# Sheet1.net
KiCad netlist of a schematic drawn in Altium Designer
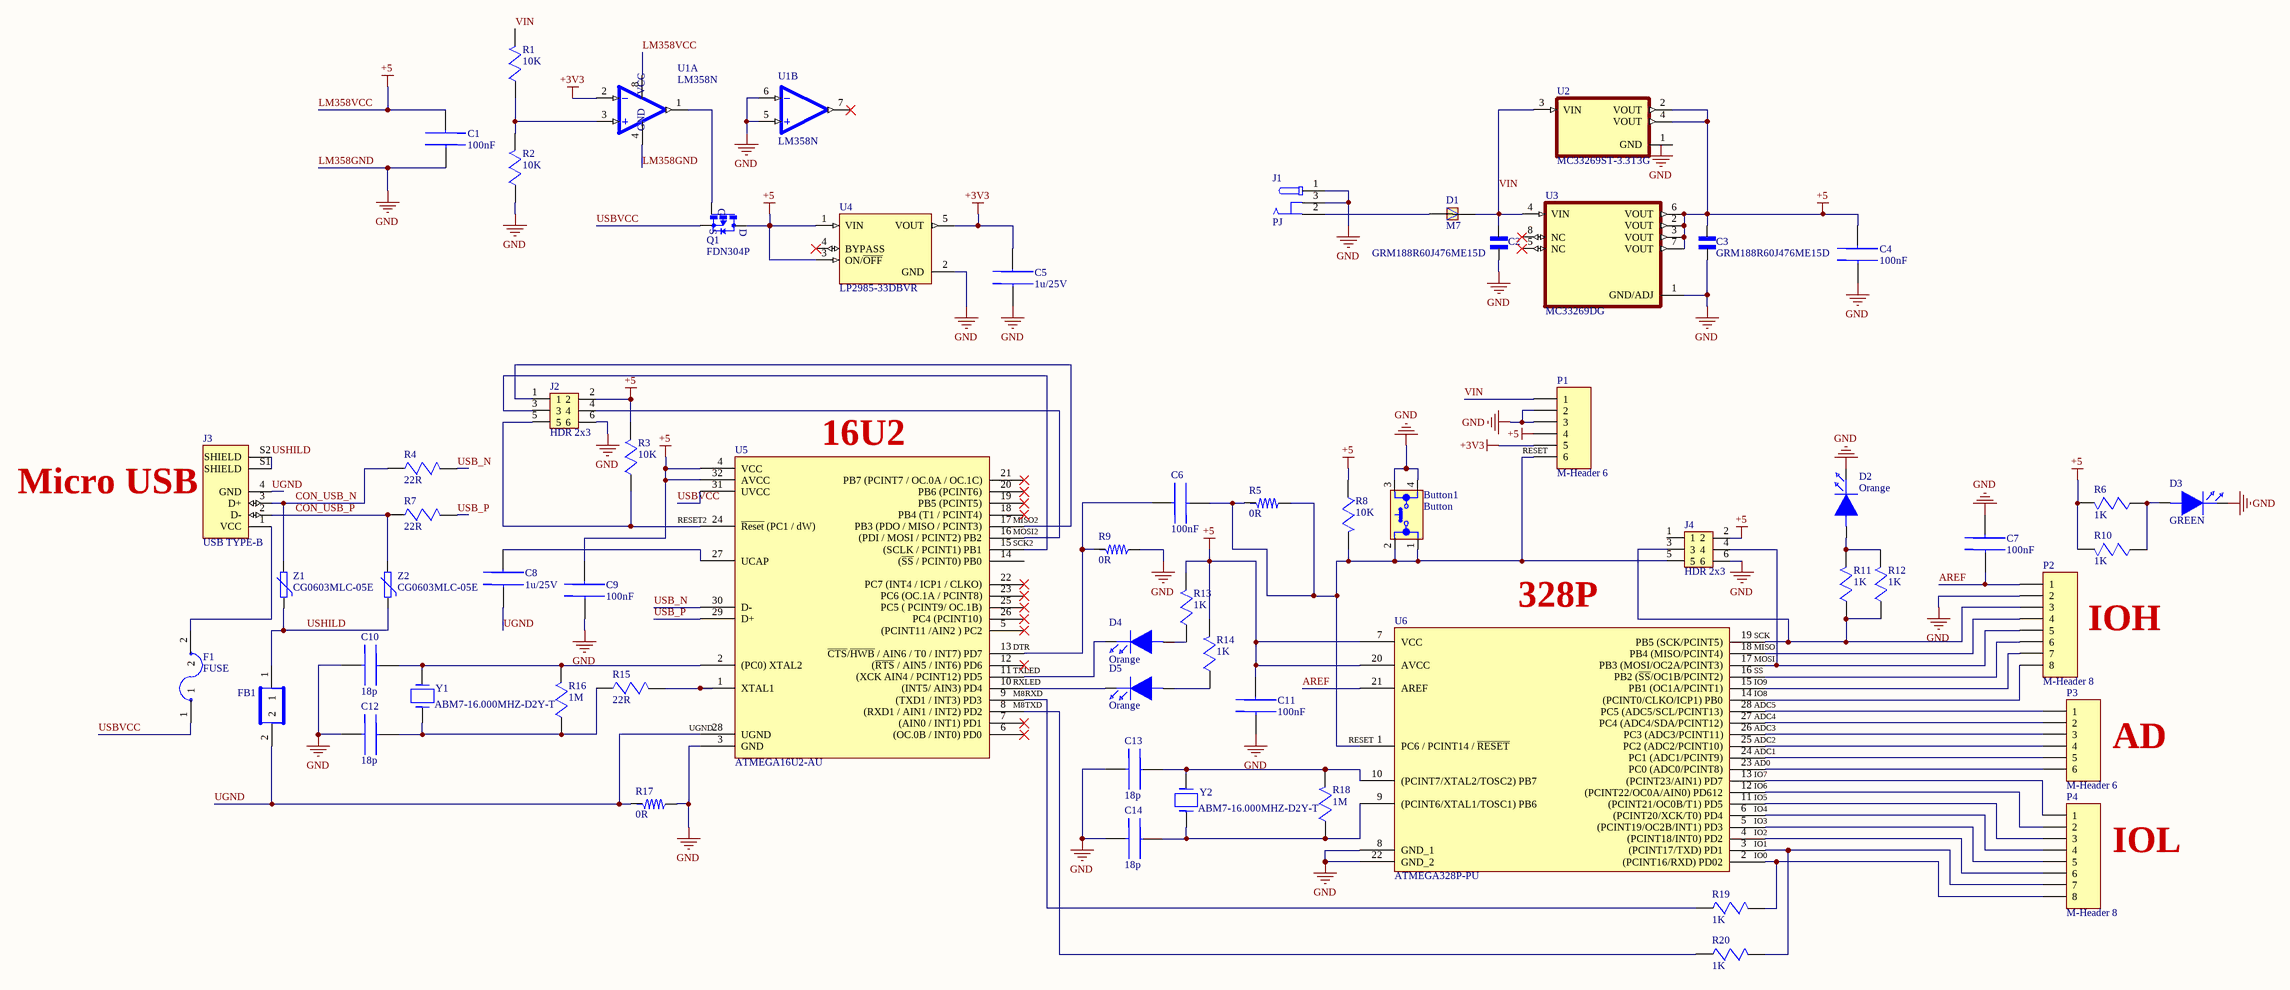
[diagram p0: Sheet1.SchDoc]

(export (version "E")
  (design (tool "Eeschema 10.0.6"))
  (components
    (comp (ref "Button1")
      (value "Button")
      (footprint "1825910-6_BUTTON")
      (description "SWITCH TACTILE SPST-NO 0.05A 24V")
      (fields
        (field (name "MANUFACTURER") "TE Connectivity Alcoswitch")
        (field (name "MANUFACTURER PART NUMBER") "1825910-6")
      )
      (libsource (lib "28_Pin Project V1.1_shematics_libraries") (part "1825910-6"))
    )
    (comp (ref "C1")
      (value "100nF")
      (footprint "C0805")
      (fields
        (field (name "MANUFACTURER") "TDK")
        (field (name "MANUFACTURER PART NUMBER") "C2012X7R1H104K085AA")
        (field (name "TOLERANCE") "10%")
      )
      (libsource (lib "28_Pin Project V1.1_shematics_libraries") (part "C2012X7R1H104K085AA"))
    )
    (comp (ref "C2")
      (value "GRM188R60J476ME15D")
      (footprint "CAPC1608X100N")
      (description "SMD capacitor X5R(EIA) with capacitance 47uF Tol.20%. Rated voltage 6.3Vdc 85C")
      (fields (field (name "MF") "Murata"))
      (libsource (lib "GRM188R60J476ME15D") (part "GRM188R60J476ME15D"))
    )
    (comp (ref "C3")
      (value "GRM188R60J476ME15D")
      (footprint "CAPC1608X100N")
      (description "SMD capacitor X5R(EIA) with capacitance 47uF Tol.20%. Rated voltage 6.3Vdc 85C")
      (fields (field (name "MF") "Murata"))
      (libsource (lib "GRM188R60J476ME15D") (part "GRM188R60J476ME15D"))
    )
    (comp (ref "C4")
      (value "100nF")
      (footprint "C0805")
      (fields
        (field (name "MANUFACTURER") "TDK")
        (field (name "MANUFACTURER PART NUMBER") "C2012X7R1H104K085AA")
        (field (name "TOLERANCE") "10%")
      )
      (libsource (lib "28_Pin Project V1.1_shematics_libraries") (part "C2012X7R1H104K085AA"))
    )
    (comp (ref "C5")
      (value "1u/25V")
      (footprint "C0805")
      (fields
        (field (name "MANUFACTURER") "TDK")
        (field (name "MANUFACTURER PART NUMBER") "C2012X5R1E105K125AA")
        (field (name "TOLERANCE") "10%")
      )
      (libsource (lib "28_Pin Project V1.1_shematics_libraries") (part "C2012X5R1E105K125AA"))
    )
    (comp (ref "C6")
      (value "100nF")
      (footprint "C0805")
      (fields
        (field (name "MANUFACTURER") "TDK")
        (field (name "MANUFACTURER PART NUMBER") "C2012X7R1H104K085AA")
        (field (name "TOLERANCE") "10%")
      )
      (libsource (lib "28_Pin Project V1.1_shematics_libraries") (part "C2012X7R1H104K085AA"))
    )
    (comp (ref "C7")
      (value "100nF")
      (footprint "C0805")
      (fields
        (field (name "MANUFACTURER") "TDK")
        (field (name "MANUFACTURER PART NUMBER") "C2012X7R1H104K085AA")
        (field (name "TOLERANCE") "10%")
      )
      (libsource (lib "28_Pin Project V1.1_shematics_libraries") (part "C2012X7R1H104K085AA"))
    )
    (comp (ref "C8")
      (value "1u/25V")
      (footprint "C0805")
      (fields
        (field (name "MANUFACTURER") "TDK")
        (field (name "MANUFACTURER PART NUMBER") "C2012X5R1E105K125AA")
        (field (name "TOLERANCE") "10%")
      )
      (libsource (lib "28_Pin Project V1.1_shematics_libraries") (part "C2012X5R1E105K125AA"))
    )
    (comp (ref "C9")
      (value "100nF")
      (footprint "C0805")
      (fields
        (field (name "MANUFACTURER") "TDK")
        (field (name "MANUFACTURER PART NUMBER") "C2012X7R1H104K085AA")
        (field (name "TOLERANCE") "10%")
      )
      (libsource (lib "28_Pin Project V1.1_shematics_libraries") (part "C2012X7R1H104K085AA"))
    )
    (comp (ref "C10")
      (value "18p")
      (footprint "C0805")
      (description "CAP CER 18PF 50V C0G/NP0 0805")
      (fields
        (field (name "MANUFACTURER") "KEMET")
        (field (name "MANUFACTURER PART NUMBER") "C0805C180J5GACTU")
      )
      (libsource (lib "28_Pin Project V1.1_shematics_libraries") (part "C0805C180J5GACTU"))
    )
    (comp (ref "C11")
      (value "100nF")
      (footprint "C0805")
      (fields
        (field (name "MANUFACTURER") "TDK")
        (field (name "MANUFACTURER PART NUMBER") "C2012X7R1H104K085AA")
        (field (name "TOLERANCE") "10%")
      )
      (libsource (lib "28_Pin Project V1.1_shematics_libraries") (part "C2012X7R1H104K085AA"))
    )
    (comp (ref "C12")
      (value "18p")
      (footprint "C0805")
      (description "CAP CER 18PF 50V C0G/NP0 0805")
      (fields
        (field (name "MANUFACTURER") "KEMET")
        (field (name "MANUFACTURER PART NUMBER") "C0805C180J5GACTU")
      )
      (libsource (lib "28_Pin Project V1.1_shematics_libraries") (part "C0805C180J5GACTU"))
    )
    (comp (ref "C13")
      (value "18p")
      (footprint "C0805")
      (description "CAP CER 18PF 50V C0G/NP0 0805")
      (fields
        (field (name "MANUFACTURER") "KEMET")
        (field (name "MANUFACTURER PART NUMBER") "C0805C180J5GACTU")
      )
      (libsource (lib "28_Pin Project V1.1_shematics_libraries") (part "C0805C180J5GACTU"))
    )
    (comp (ref "C14")
      (value "18p")
      (footprint "C0805")
      (description "CAP CER 18PF 50V C0G/NP0 0805")
      (fields
        (field (name "MANUFACTURER") "KEMET")
        (field (name "MANUFACTURER PART NUMBER") "C0805C180J5GACTU")
      )
      (libsource (lib "28_Pin Project V1.1_shematics_libraries") (part "C0805C180J5GACTU"))
    )
    (comp (ref "D1")
      (value "M7")
      (footprint "DIOM505270X240")
      (description "Diode, SMA, 1000V, 1A, 150Â°C")
      (fields (field (name "MF") "Diotec Semiconductor"))
      (libsource (lib "M7") (part "M7"))
    )
    (comp (ref "D2")
      (value "Orange")
      (footprint "Orange_LED")
      (description "OSRAM - LO L29K-H2K1-24-Z - SMARTLED 0603 ORANGE")
      (fields
        (field (name "MANUFACTURER") "Osram Opto")
        (field (name "MANUFACTURER PART NUMBER") "LOL29K-H2K1-24-Z")
      )
      (libsource (lib "28_Pin Project V1.1_shematics_libraries") (part "LOL29K-H2K1-24-Z"))
    )
    (comp (ref "D3")
      (value "GREEN")
      (footprint "Orange_LED")
      (description "LED Uni-Color Green 572nm 2-Pin Chip 0603(1608Metric) T/R")
      (fields
        (field (name "MANUFACTURER") "Osram Opto")
        (field (name "MANUFACTURER PART NUMBER") "LGL29K-G2J1-24-Z")
      )
      (libsource (lib "28_Pin Project V1.1_shematics_libraries") (part "LGL29K-G2J1-24-Z"))
    )
    (comp (ref "D4")
      (value "Orange")
      (footprint "Orange_LED")
      (description "OSRAM - LO L29K-H2K1-24-Z - SMARTLED 0603 ORANGE")
      (fields
        (field (name "MANUFACTURER") "Osram Opto")
        (field (name "MANUFACTURER PART NUMBER") "LOL29K-H2K1-24-Z")
      )
      (libsource (lib "28_Pin Project V1.1_shematics_libraries") (part "LOL29K-H2K1-24-Z"))
    )
    (comp (ref "D5")
      (value "Orange")
      (footprint "Orange_LED")
      (description "OSRAM - LO L29K-H2K1-24-Z - SMARTLED 0603 ORANGE")
      (fields
        (field (name "MANUFACTURER") "Osram Opto")
        (field (name "MANUFACTURER PART NUMBER") "LOL29K-H2K1-24-Z")
      )
      (libsource (lib "28_Pin Project V1.1_shematics_libraries") (part "LOL29K-H2K1-24-Z"))
    )
    (comp (ref "F1")
      (value "FUSE")
      (footprint "FUSM4632X85")
      (description "Polymeric PTC Resettable Fuse 15V 500 mA Ih Surface Mount 1812 (4532 Metric), Concave")
      (fields (field (name "MP") "MF-MSMF050-2") (field (name "MF") "Bourns"))
      (libsource (lib "ARDUINO-UNO") (part "FUSE"))
    )
    (comp (ref "FB1")
      (value "~")
      (footprint "C0805")
      (description "FERRITE BEAD 600 OHM 0805 1LN")
      (fields
        (field (name "MANUFACTURER") "TDK")
        (field (name "MANUFACTURER PART NUMBER") "MPZ2012S601AT000")
      )
      (libsource (lib "28_Pin Project V1.1_shematics_libraries") (part "MPZ2012S601AT000"))
    )
    (comp (ref "J1")
      (value "PJ")
      (footprint "MPD_EJ503A")
      (description "Power Barrel Connector Jack 2.10mm ID (0.083), 5.50mm OD (0.217) Through Hole, Right Angle")
      (fields (field (name "MF") "MPD") (field (name "MP") "EJ503A"))
      (libsource (lib "ARDUINO-UNO") (part "PJ"))
    )
    (comp (ref "J2")
      (value "HDR 2x3")
      (footprint "HDR_2x3_2.55mm")
      (description "CONN HEADER 6POS .100 STR 30AU")
      (fields
        (field (name "MANUFACTURER") "Amphenol FCI")
        (field (name "MANUFACTURER PART NUMBER") "67997-106HLF")
      )
      (libsource (lib "28_Pin Project V1.1_shematics_libraries") (part "67997-106HLF"))
    )
    (comp (ref "J3")
      (value "USB TYPE-B")
      (footprint "SAMTEC_USB-B-S-X-X-TH")
      (description "USB-B (USB TYPE-B) USB 2.0 Receptacle Connector 4 Position Through Hole, Right Angle")
      (fields (field (name "MF") "Samtec") (field (name "MP") "USB-B-S-F-W-TH-TR"))
      (libsource (lib "ARDUINO-UNO") (part "USB TYPE-B"))
    )
    (comp (ref "J4")
      (value "HDR 2x3")
      (footprint "HDR_2x3_2.55mm")
      (description "CONN HEADER 6POS .100 STR 30AU")
      (fields
        (field (name "MANUFACTURER") "Amphenol FCI")
        (field (name "MANUFACTURER PART NUMBER") "67997-106HLF")
      )
      (libsource (lib "28_Pin Project V1.1_shematics_libraries") (part "67997-106HLF"))
    )
    (comp (ref "P1")
      (value "M-Header 6")
      (footprint "M-Header 6")
      (libsource (lib "ARDUINO-UNO") (part "M-Header 6"))
    )
    (comp (ref "P2")
      (value "M-Header 8")
      (footprint "M-Header 8")
      (libsource (lib "ARDUINO-UNO") (part "M-Header 8"))
    )
    (comp (ref "P3")
      (value "M-Header 6")
      (footprint "M-Header 6")
      (libsource (lib "ARDUINO-UNO") (part "M-Header 6"))
    )
    (comp (ref "P4")
      (value "M-Header 8")
      (footprint "M-Header 8")
      (libsource (lib "ARDUINO-UNO") (part "M-Header 8"))
    )
    (comp (ref "Q1")
      (value "FDN304P")
      (footprint "SSOT-3")
      (description "P-Channel 20 V 2.4A (Ta) 500mW (Ta) Surface Mount SOT-23-3")
      (fields (field (name "MF") "onsemi"))
      (libsource (lib "FDN304P") (part "FDN304P"))
    )
    (comp (ref "R1")
      (value "10K")
      (footprint "R0805")
      (description "RES SMD 10K OHM 1% 1/8W 0805")
      (fields
        (field (name "MANUFACTURER") "Yageo")
        (field (name "MANUFACTURER PART NUMBER") "RC0805FR-0710KL")
      )
      (libsource (lib "28_Pin Project V1.1_shematics_libraries") (part "RC0805FR-0710KL"))
    )
    (comp (ref "R2")
      (value "10K")
      (footprint "R0805")
      (description "RES SMD 10K OHM 1% 1/8W 0805")
      (fields
        (field (name "MANUFACTURER") "Yageo")
        (field (name "MANUFACTURER PART NUMBER") "RC0805FR-0710KL")
      )
      (libsource (lib "28_Pin Project V1.1_shematics_libraries") (part "RC0805FR-0710KL"))
    )
    (comp (ref "R3")
      (value "10K")
      (footprint "R0805")
      (description "RES SMD 10K OHM 1% 1/8W 0805")
      (fields
        (field (name "MANUFACTURER") "Yageo")
        (field (name "MANUFACTURER PART NUMBER") "RC0805FR-0710KL")
      )
      (libsource (lib "28_Pin Project V1.1_shematics_libraries") (part "RC0805FR-0710KL"))
    )
    (comp (ref "R4")
      (value "22R")
      (footprint "R0805")
      (description "RES SMD 22 OHM 1% 1/8W 0805")
      (fields
        (field (name "MANUFACTURER") "Yageo")
        (field (name "MANUFACTURER PART NUMBER") "RC0805FR-0722RL")
      )
      (libsource (lib "28_Pin Project V1.1_shematics_libraries") (part "RC0805FR-0722RL"))
    )
    (comp (ref "R5")
      (value "0R")
      (footprint "RESC2012X60N")
      (description "CR0805 SMD Thick Film Resistor,1 Kilohms,Pwr-Rtg 0.125 W,Tol 1%,SMT ¦ Bourns CR0805-FX-1001ELF")
      (fields (field (name "MF") "Bourns") (field (name "MP") "CR0805-FX-1001ELF"))
      (libsource (lib "ARDUINO-UNO") (part "RES"))
    )
    (comp (ref "R6")
      (value "1K")
      (footprint "R0805")
      (fields
        (field (name "MANUFACTURER") "Yageo")
        (field (name "MANUFACTURER PART NUMBER") "RC0805FR-071KL")
        (field (name "TOLERANCE") "1%")
      )
      (libsource (lib "28_Pin Project V1.1_shematics_libraries") (part "RC0805FR-071KL"))
    )
    (comp (ref "R7")
      (value "22R")
      (footprint "R0805")
      (description "RES SMD 22 OHM 1% 1/8W 0805")
      (fields
        (field (name "MANUFACTURER") "Yageo")
        (field (name "MANUFACTURER PART NUMBER") "RC0805FR-0722RL")
      )
      (libsource (lib "28_Pin Project V1.1_shematics_libraries") (part "RC0805FR-0722RL"))
    )
    (comp (ref "R8")
      (value "10K")
      (footprint "R0805")
      (description "RES SMD 10K OHM 1% 1/8W 0805")
      (fields
        (field (name "MANUFACTURER") "Yageo")
        (field (name "MANUFACTURER PART NUMBER") "RC0805FR-0710KL")
      )
      (libsource (lib "28_Pin Project V1.1_shematics_libraries") (part "RC0805FR-0710KL"))
    )
    (comp (ref "R9")
      (value "0R")
      (footprint "RESC2012X60N")
      (description "CR0805 SMD Thick Film Resistor,1 Kilohms,Pwr-Rtg 0.125 W,Tol 1%,SMT ¦ Bourns CR0805-FX-1001ELF")
      (fields (field (name "MF") "Bourns") (field (name "MP") "CR0805-FX-1001ELF"))
      (libsource (lib "ARDUINO-UNO") (part "RES"))
    )
    (comp (ref "R10")
      (value "1K")
      (footprint "R0805")
      (fields
        (field (name "MANUFACTURER") "Yageo")
        (field (name "MANUFACTURER PART NUMBER") "RC0805FR-071KL")
        (field (name "TOLERANCE") "1%")
      )
      (libsource (lib "28_Pin Project V1.1_shematics_libraries") (part "RC0805FR-071KL"))
    )
    (comp (ref "R11")
      (value "1K")
      (footprint "R0805")
      (fields
        (field (name "MANUFACTURER") "Yageo")
        (field (name "MANUFACTURER PART NUMBER") "RC0805FR-071KL")
        (field (name "TOLERANCE") "1%")
      )
      (libsource (lib "28_Pin Project V1.1_shematics_libraries") (part "RC0805FR-071KL"))
    )
    (comp (ref "R12")
      (value "1K")
      (footprint "R0805")
      (fields
        (field (name "MANUFACTURER") "Yageo")
        (field (name "MANUFACTURER PART NUMBER") "RC0805FR-071KL")
        (field (name "TOLERANCE") "1%")
      )
      (libsource (lib "28_Pin Project V1.1_shematics_libraries") (part "RC0805FR-071KL"))
    )
    (comp (ref "R13")
      (value "1K")
      (footprint "R0805")
      (fields
        (field (name "MANUFACTURER") "Yageo")
        (field (name "MANUFACTURER PART NUMBER") "RC0805FR-071KL")
        (field (name "TOLERANCE") "1%")
      )
      (libsource (lib "28_Pin Project V1.1_shematics_libraries") (part "RC0805FR-071KL"))
    )
    (comp (ref "R14")
      (value "1K")
      (footprint "R0805")
      (fields
        (field (name "MANUFACTURER") "Yageo")
        (field (name "MANUFACTURER PART NUMBER") "RC0805FR-071KL")
        (field (name "TOLERANCE") "1%")
      )
      (libsource (lib "28_Pin Project V1.1_shematics_libraries") (part "RC0805FR-071KL"))
    )
    (comp (ref "R15")
      (value "22R")
      (footprint "R0805")
      (description "RES SMD 22 OHM 1% 1/8W 0805")
      (fields
        (field (name "MANUFACTURER") "Yageo")
        (field (name "MANUFACTURER PART NUMBER") "RC0805FR-0722RL")
      )
      (libsource (lib "28_Pin Project V1.1_shematics_libraries") (part "RC0805FR-0722RL"))
    )
    (comp (ref "R16")
      (value "1M")
      (footprint "R0805")
      (description "Res Thick Film 0805 1M Ohm 1% 0.125W(1/8W) ±100ppm/C Epoxy SMD T/R")
      (fields
        (field (name "MANUFACTURER") "Yageo Phycomp")
        (field (name "MANUFACTURER PART NUMBER") "RC0805FR-071ML")
      )
      (libsource (lib "28_Pin Project V1.1_shematics_libraries") (part "RC0805FR-071ML"))
    )
    (comp (ref "R17")
      (value "0R")
      (footprint "RESC2012X60N")
      (description "CR0805 SMD Thick Film Resistor,1 Kilohms,Pwr-Rtg 0.125 W,Tol 1%,SMT ¦ Bourns CR0805-FX-1001ELF")
      (fields (field (name "MF") "Bourns") (field (name "MP") "CR0805-FX-1001ELF"))
      (libsource (lib "ARDUINO-UNO") (part "RES"))
    )
    (comp (ref "R18")
      (value "1M")
      (footprint "R0805")
      (description "Res Thick Film 0805 1M Ohm 1% 0.125W(1/8W) ±100ppm/C Epoxy SMD T/R")
      (fields
        (field (name "MANUFACTURER") "Yageo Phycomp")
        (field (name "MANUFACTURER PART NUMBER") "RC0805FR-071ML")
      )
      (libsource (lib "28_Pin Project V1.1_shematics_libraries") (part "RC0805FR-071ML"))
    )
    (comp (ref "R19")
      (value "1K")
      (footprint "R0805")
      (fields
        (field (name "MANUFACTURER") "Yageo")
        (field (name "MANUFACTURER PART NUMBER") "RC0805FR-071KL")
        (field (name "TOLERANCE") "1%")
      )
      (libsource (lib "28_Pin Project V1.1_shematics_libraries") (part "RC0805FR-071KL"))
    )
    (comp (ref "R20")
      (value "1K")
      (footprint "R0805")
      (fields
        (field (name "MANUFACTURER") "Yageo")
        (field (name "MANUFACTURER PART NUMBER") "RC0805FR-071KL")
        (field (name "TOLERANCE") "1%")
      )
      (libsource (lib "28_Pin Project V1.1_shematics_libraries") (part "RC0805FR-071KL"))
    )
    (comp (ref "U1")
      (value "LM358N")
      (footprint "DIP762W46P254L960H508Q8")
      (description "IC OPAMP GP 8DIP")
      (fields (field (name "MF") "STMicroelectronics"))
      (libsource (lib "LM358N") (part "LM358N"))
    )
    (comp (ref "U2")
      (value "MC33269ST-3.3T3G")
      (footprint "SOT230P700X175-4N")
      (description "Voltage Regulators, LDO, 3.3V ADJ 800mA ¦ ON Semiconductor MC33269ST-3.3T3G")
      (fields (field (name "MF") "ON Semiconductor"))
      (libsource (lib "ARDUINO-UNO") (part "MC33269ST-3.3T3G"))
    )
    (comp (ref "U3")
      (value "MC33269DG")
      (footprint "SOIC127P600X175-8N")
      (description "Linear Voltage Regulator IC Positive Adjustable 1 Output 800mA 8-SOIC")
      (fields (field (name "MF") "ON Semiconductor"))
      (libsource (lib "ARDUINO-UNO") (part "MC33269DG"))
    )
    (comp (ref "U4")
      (value "LP2985-33DBVR")
      (footprint "SOT95P280X145-5N")
      (description "150-mA, 16-V, low-dropout voltage regulator with enable")
      (fields (field (name "MF") "Texas Instruments"))
      (libsource (lib "LP2985-33DBVR") (part "LP2985-33DBVR"))
    )
    (comp (ref "U5")
      (value "ATMEGA16U2-AU")
      (footprint "TQFP32")
      (description "MICROCHIP - ATMEGA16U2-AU - MCU, 8BIT, MEGAAVR, 16MHZ, TQFP-32")
      (fields (field (name "MANUFACTURER") "Microchip / Atmel"))
      (libsource (lib "28_Pin Project V1.1_shematics_libraries") (part "ATMEGA16U2-AU"))
    )
    (comp (ref "U6")
      (value "ATMEGA328P-PU")
      (footprint "27_DIP_7.62mm")
      (description "ATMEGA328P-PU; 8 bit Microcontroller AVR 20MHz 1; 32kb Flash; 2kb RAM; I2C SPI 2")
      (fields (field (name "MANUFACTURER") "Microchip / Atmel"))
      (libsource (lib "28_Pin Project V1.1_shematics_libraries") (part "ATMEGA328P-PU"))
    )
    (comp (ref "Y1")
      (value "ABM7-16.000MHZ-D2Y-T")
      (footprint "Crystal_16MHz_footprint")
      (description "CRYSTAL 16.0000MHZ 18PF SMD")
      (fields (field (name "MANUFACTURER") "Abracon") (field (name "TOLERANCE") "20ppm"))
      (libsource (lib "28_Pin Project V1.1_shematics_libraries") (part "ABM7-16.000MHZ-D2Y-T"))
    )
    (comp (ref "Y2")
      (value "ABM7-16.000MHZ-D2Y-T")
      (footprint "Crystal_16MHz_footprint")
      (description "CRYSTAL 16.0000MHZ 18PF SMD")
      (fields (field (name "MANUFACTURER") "Abracon") (field (name "TOLERANCE") "20ppm"))
      (libsource (lib "28_Pin Project V1.1_shematics_libraries") (part "ABM7-16.000MHZ-D2Y-T"))
    )
    (comp (ref "Z1")
      (value "CG0603MLC-05E")
      (footprint "R0603")
      (description "VARISTOR 0603")
      (fields (field (name "MANUFACTURER") "Bourns") (field (name "VOLTAGE") "5V"))
      (libsource (lib "28_Pin Project V1.1_shematics_libraries") (part "CG0603MLC-05E"))
    )
    (comp (ref "Z2")
      (value "CG0603MLC-05E")
      (footprint "R0603")
      (description "VARISTOR 0603")
      (fields (field (name "MANUFACTURER") "Bourns") (field (name "VOLTAGE") "5V"))
      (libsource (lib "28_Pin Project V1.1_shematics_libraries") (part "CG0603MLC-05E"))
    )
  )
  (nets
    (net (code "1") (name "+3V3") (class "Default")
      (node (ref "C5") (pin "2") (pinfunction "2_2") (pintype "passive"))
      (node (ref "P1") (pin "5") (pinfunction "5_5") (pintype "passive"))
      (node (ref "U1") (pin "2") (pinfunction "1IN-_2") (pintype "input"))
      (node (ref "U4") (pin "5") (pinfunction "VOUT_5") (pintype "output"))
    )
    (net (code "2") (name "+5") (class "Default")
      (node (ref "C1") (pin "1") (pinfunction "1_1") (pintype "passive"))
      (node (ref "C11") (pin "2") (pinfunction "2_2") (pintype "passive"))
      (node (ref "C3") (pin "2") (pinfunction "2_2") (pintype "passive"))
      (node (ref "C4") (pin "2") (pinfunction "2_2") (pintype "passive"))
      (node (ref "C9") (pin "2") (pinfunction "2_2") (pintype "passive"))
      (node (ref "J2") (pin "2") (pinfunction "2_2") (pintype "passive"))
      (node (ref "J4") (pin "2") (pinfunction "2_2") (pintype "passive"))
      (node (ref "P1") (pin "4") (pinfunction "4_4") (pintype "passive"))
      (node (ref "Q1") (pin "3") (pinfunction "D_3") (pintype "passive"))
      (node (ref "R10") (pin "2") (pinfunction "2_2") (pintype "passive"))
      (node (ref "R13") (pin "2") (pinfunction "2_2") (pintype "passive"))
      (node (ref "R14") (pin "2") (pinfunction "2_2") (pintype "passive"))
      (node (ref "R3") (pin "2") (pinfunction "2_2") (pintype "passive"))
      (node (ref "R6") (pin "2") (pinfunction "2_2") (pintype "passive"))
      (node (ref "R8") (pin "1") (pinfunction "1_1") (pintype "passive"))
      (node (ref "U1") (pin "8") (pinfunction "VCC_8") (pintype "power_in"))
      (node (ref "U2") (pin "2") (pinfunction "VOUT_2") (pintype "output"))
      (node (ref "U2") (pin "4") (pinfunction "VOUT_4") (pintype "output"))
      (node (ref "U3") (pin "2") (pinfunction "VOUT_2") (pintype "output"))
      (node (ref "U3") (pin "3") (pinfunction "VOUT_3") (pintype "output"))
      (node (ref "U3") (pin "6") (pinfunction "VOUT_6") (pintype "output"))
      (node (ref "U3") (pin "7") (pinfunction "VOUT_7") (pintype "output"))
      (node (ref "U4") (pin "1") (pinfunction "VIN_1") (pintype "input"))
      (node (ref "U4") (pin "3") (pinfunction "ON/~{OFF}_3") (pintype "input"))
      (node (ref "U5") (pin "32") (pinfunction "AVCC_32") (pintype "passive"))
      (node (ref "U5") (pin "4") (pinfunction "VCC_4") (pintype "passive"))
      (node (ref "U6") (pin "20") (pinfunction "AVCC_20") (pintype "passive"))
      (node (ref "U6") (pin "7") (pinfunction "VCC_7") (pintype "passive"))
    )
    (net (code "3") (name "/AREF") (class "Default")
      (node (ref "C7") (pin "1") (pinfunction "1_1") (pintype "passive"))
      (node (ref "P2") (pin "1") (pinfunction "1_1") (pintype "passive"))
      (node (ref "U6") (pin "21") (pinfunction "AREF_21") (pintype "passive"))
    )
    (net (code "4") (name "/CON_USB_N") (class "Default")
      (node (ref "J3") (pin "3") (pinfunction "D+_3") (pintype "bidirectional"))
      (node (ref "R4") (pin "1") (pinfunction "1_1") (pintype "passive"))
      (node (ref "Z1") (pin "1") (pinfunction "1_1") (pintype "passive"))
    )
    (net (code "5") (name "/CON_USB_P") (class "Default")
      (node (ref "J3") (pin "2") (pinfunction "D-_2") (pintype "bidirectional"))
      (node (ref "R7") (pin "1") (pinfunction "1_1") (pintype "passive"))
      (node (ref "Z2") (pin "1") (pinfunction "1_1") (pintype "passive"))
    )
    (net (code "6") (name "/UGND") (class "Default")
      (node (ref "C8") (pin "1") (pinfunction "1_1") (pintype "passive"))
      (node (ref "FB1") (pin "2") (pinfunction "2_2") (pintype "passive"))
      (node (ref "J3") (pin "4") (pinfunction "GND_4") (pintype "power_in"))
      (node (ref "R17") (pin "1") (pinfunction "1_1") (pintype "passive"))
      (node (ref "U5") (pin "28") (pinfunction "UGND_28") (pintype "passive"))
    )
    (net (code "7") (name "/USBVCC") (class "Default")
      (node (ref "F1") (pin "1") (pinfunction "1_1") (pintype "passive"))
      (node (ref "Q1") (pin "2") (pinfunction "S_2") (pintype "passive"))
      (node (ref "U5") (pin "31") (pinfunction "UVCC_31") (pintype "passive"))
    )
    (net (code "8") (name "/USB_N") (class "Default")
      (node (ref "R4") (pin "2") (pinfunction "2_2") (pintype "passive"))
      (node (ref "U5") (pin "30") (pinfunction "D-_30") (pintype "passive"))
    )
    (net (code "9") (name "/USB_P") (class "Default")
      (node (ref "R7") (pin "2") (pinfunction "2_2") (pintype "passive"))
      (node (ref "U5") (pin "29") (pinfunction "D+_29") (pintype "passive"))
    )
    (net (code "10") (name "/USHILD") (class "Default")
      (node (ref "FB1") (pin "1") (pinfunction "1_1") (pintype "passive"))
      (node (ref "J3") (pin "S1") (pinfunction "SHIELD_S1") (pintype "passive"))
      (node (ref "J3") (pin "S2") (pinfunction "SHIELD_S2") (pintype "passive"))
      (node (ref "Z1") (pin "2") (pinfunction "2_2") (pintype "passive"))
      (node (ref "Z2") (pin "2") (pinfunction "2_2") (pintype "passive"))
    )
    (net (code "11") (name "/VIN") (class "Default")
      (node (ref "C2") (pin "2") (pinfunction "2_2") (pintype "passive"))
      (node (ref "D1") (pin "C") (pinfunction "C_C") (pintype "passive"))
      (node (ref "P1") (pin "1") (pinfunction "1_1") (pintype "passive"))
      (node (ref "R1") (pin "2") (pinfunction "2_2") (pintype "passive"))
      (node (ref "U2") (pin "3") (pinfunction "VIN_3") (pintype "input"))
      (node (ref "U3") (pin "4") (pinfunction "VIN_4") (pintype "input"))
    )
    (net (code "12") (name "GND") (class "Default")
      (node (ref "Button1") (pin "3") (pinfunction "3_3") (pintype "passive"))
      (node (ref "Button1") (pin "4") (pinfunction "4_4") (pintype "passive"))
      (node (ref "C1") (pin "2") (pinfunction "2_2") (pintype "passive"))
      (node (ref "C10") (pin "1") (pinfunction "1_1") (pintype "passive"))
      (node (ref "C11") (pin "1") (pinfunction "1_1") (pintype "passive"))
      (node (ref "C12") (pin "1") (pinfunction "1_1") (pintype "passive"))
      (node (ref "C13") (pin "1") (pinfunction "1_1") (pintype "passive"))
      (node (ref "C14") (pin "1") (pinfunction "1_1") (pintype "passive"))
      (node (ref "C2") (pin "1") (pinfunction "1_1") (pintype "passive"))
      (node (ref "C3") (pin "1") (pinfunction "1_1") (pintype "passive"))
      (node (ref "C4") (pin "1") (pinfunction "1_1") (pintype "passive"))
      (node (ref "C5") (pin "1") (pinfunction "1_1") (pintype "passive"))
      (node (ref "C7") (pin "2") (pinfunction "2_2") (pintype "passive"))
      (node (ref "C9") (pin "1") (pinfunction "1_1") (pintype "passive"))
      (node (ref "D2") (pin "1") (pinfunction "Cathode_1") (pintype "passive"))
      (node (ref "D3") (pin "1") (pinfunction "Cathode_1") (pintype "passive"))
      (node (ref "J1") (pin "1") (pinfunction "1_1") (pintype "passive"))
      (node (ref "J1") (pin "3") (pinfunction "3_3") (pintype "passive"))
      (node (ref "J2") (pin "6") (pinfunction "6_6") (pintype "passive"))
      (node (ref "J4") (pin "6") (pinfunction "6_6") (pintype "passive"))
      (node (ref "P1") (pin "2") (pinfunction "2_2") (pintype "passive"))
      (node (ref "P1") (pin "3") (pinfunction "3_3") (pintype "passive"))
      (node (ref "P2") (pin "2") (pinfunction "2_2") (pintype "passive"))
      (node (ref "R17") (pin "2") (pinfunction "2_2") (pintype "passive"))
      (node (ref "R2") (pin "1") (pinfunction "1_1") (pintype "passive"))
      (node (ref "R9") (pin "2") (pinfunction "2_2") (pintype "passive"))
      (node (ref "U1") (pin "4") (pinfunction "GND_4") (pintype "power_in"))
      (node (ref "U1") (pin "5") (pinfunction "2IN+_5") (pintype "input"))
      (node (ref "U1") (pin "6") (pinfunction "2IN-_6") (pintype "input"))
      (node (ref "U3") (pin "1") (pinfunction "GND/ADJ_1") (pintype "power_in"))
      (node (ref "U4") (pin "2") (pinfunction "GND_2") (pintype "power_in"))
      (node (ref "U5") (pin "3") (pinfunction "GND_3") (pintype "passive"))
      (node (ref "U6") (pin "22") (pinfunction "GND_2_22") (pintype "passive"))
      (node (ref "U6") (pin "8") (pinfunction "GND_1_8") (pintype "passive"))
    )
    (net (code "13") (name "Net-(C12-Pad2)") (class "Default")
      (node (ref "C12") (pin "2") (pinfunction "2_2") (pintype "passive"))
      (node (ref "R15") (pin "1") (pinfunction "1_1") (pintype "passive"))
      (node (ref "R16") (pin "1") (pinfunction "1_1") (pintype "passive"))
      (node (ref "Y1") (pin "1") (pinfunction "1_1") (pintype "passive"))
    )
    (net (code "14") (name "Net-(D1-PadA)") (class "Default")
      (node (ref "D1") (pin "A") (pinfunction "A_A") (pintype "passive"))
      (node (ref "J1") (pin "2") (pinfunction "2_2") (pintype "passive"))
    )
    (net (code "15") (name "Net-(D2-Anode)") (class "Default")
      (node (ref "D2") (pin "2") (pinfunction "Anode_2") (pintype "passive"))
      (node (ref "R11") (pin "2") (pinfunction "2_2") (pintype "passive"))
      (node (ref "R12") (pin "2") (pinfunction "2_2") (pintype "passive"))
    )
    (net (code "16") (name "Net-(D3-Anode)") (class "Default")
      (node (ref "D3") (pin "2") (pinfunction "Anode_2") (pintype "passive"))
      (node (ref "R10") (pin "1") (pinfunction "1_1") (pintype "passive"))
      (node (ref "R6") (pin "1") (pinfunction "1_1") (pintype "passive"))
    )
    (net (code "17") (name "Net-(D4-Anode)") (class "Default")
      (node (ref "D4") (pin "2") (pinfunction "Anode_2") (pintype "passive"))
      (node (ref "R13") (pin "1") (pinfunction "1_1") (pintype "passive"))
    )
    (net (code "18") (name "Net-(D4-Cathode)") (class "Default")
      (node (ref "D4") (pin "1") (pinfunction "Cathode_1") (pintype "passive"))
      (node (ref "U5") (pin "11") (pinfunction "(XCK_AIN4_/_PCINT12)_PD5_11") (pintype "passive"))
    )
    (net (code "19") (name "Net-(D5-Anode)") (class "Default")
      (node (ref "D5") (pin "2") (pinfunction "Anode_2") (pintype "passive"))
      (node (ref "R14") (pin "1") (pinfunction "1_1") (pintype "passive"))
    )
    (net (code "20") (name "Net-(D5-Cathode)") (class "Default")
      (node (ref "D5") (pin "1") (pinfunction "Cathode_1") (pintype "passive"))
      (node (ref "U5") (pin "10") (pinfunction "(INT5/_AIN3)_PD4_10") (pintype "passive"))
    )
    (net (code "21") (name "Net-(J3-VCC)") (class "Default")
      (node (ref "F1") (pin "2") (pinfunction "2_2") (pintype "passive"))
      (node (ref "J3") (pin "1") (pinfunction "VCC_1") (pintype "power_in"))
    )
    (net (code "22") (name "Net-(Q1-G)") (class "Default")
      (node (ref "Q1") (pin "1") (pinfunction "G_1") (pintype "passive"))
      (node (ref "U1") (pin "1") (pinfunction "1OUT_1") (pintype "output"))
    )
    (net (code "23") (name "Net-(U1A-1IN+)") (class "Default")
      (node (ref "R1") (pin "1") (pinfunction "1_1") (pintype "passive"))
      (node (ref "R2") (pin "2") (pinfunction "2_2") (pintype "passive"))
      (node (ref "U1") (pin "3") (pinfunction "1IN+_3") (pintype "input"))
    )
    (net (code "24") (name "Net-(U5-(PC0)_XTAL2)") (class "Default")
      (node (ref "C10") (pin "2") (pinfunction "2_2") (pintype "passive"))
      (node (ref "R16") (pin "2") (pinfunction "2_2") (pintype "passive"))
      (node (ref "U5") (pin "2") (pinfunction "(PC0)_XTAL2_2") (pintype "passive"))
      (node (ref "Y1") (pin "2") (pinfunction "2_2") (pintype "passive"))
    )
    (net (code "25") (name "Net-(U5-(PDI_{slash}_MOSI_{slash}_PCINT2)_PB2)") (class "Default")
      (node (ref "J2") (pin "4") (pinfunction "4_4") (pintype "passive"))
      (node (ref "U5") (pin "16") (pinfunction "(PDI_/_MOSI_/_PCINT2)_PB2_16") (pintype "passive"))
    )
    (net (code "26") (name "Net-(U5-(RXD1_{slash}_AIN1_{slash}_INT2)_PD2)") (class "Default")
      (node (ref "R20") (pin "1") (pinfunction "1_1") (pintype "passive"))
      (node (ref "U5") (pin "8") (pinfunction "(RXD1_/_AIN1_/_INT2)_PD2_8") (pintype "passive"))
    )
    (net (code "27") (name "Net-(U5-(SCLK_{slash}_PCINT1)_PB1)") (class "Default")
      (node (ref "J2") (pin "3") (pinfunction "3_3") (pintype "passive"))
      (node (ref "U5") (pin "15") (pinfunction "(SCLK_/_PCINT1)_PB1_15") (pintype "passive"))
    )
    (net (code "28") (name "Net-(U5-(TXD1_{slash}_INT3)_PD3)") (class "Default")
      (node (ref "R19") (pin "1") (pinfunction "1_1") (pintype "passive"))
      (node (ref "U5") (pin "9") (pinfunction "(TXD1_/_INT3)_PD3_9") (pintype "passive"))
    )
    (net (code "29") (name "Net-(U5-PB3_(PDO_{slash}_MISO_{slash}_PCINT3))") (class "Default")
      (node (ref "J2") (pin "1") (pinfunction "1_1") (pintype "passive"))
      (node (ref "U5") (pin "17") (pinfunction "PB3_(PDO_/_MISO_/_PCINT3)_17") (pintype "passive"))
    )
    (net (code "30") (name "Net-(U5-UCAP)") (class "Default")
      (node (ref "C8") (pin "2") (pinfunction "2_2") (pintype "passive"))
      (node (ref "U5") (pin "27") (pinfunction "UCAP_27") (pintype "passive"))
    )
    (net (code "31") (name "Net-(U5-XTAL1)") (class "Default")
      (node (ref "R15") (pin "2") (pinfunction "2_2") (pintype "passive"))
      (node (ref "U5") (pin "1") (pinfunction "XTAL1_1") (pintype "passive"))
    )
    (net (code "32") (name "Net-(U5-~{CTS}{slash}~{HWB}_{slash}_AIN6_{slash}_T0_{slash}_INT7)_PD7)") (class "Default")
      (node (ref "C6") (pin "2") (pinfunction "2_2") (pintype "passive"))
      (node (ref "R9") (pin "1") (pinfunction "1_1") (pintype "passive"))
      (node (ref "U5") (pin "13") (pinfunction "~{CTS}/~{HWB}_/_AIN6_/_T0_/_INT7)_PD7_13") (pintype "passive"))
    )
    (net (code "33") (name "Net-(U5-~{Reset}_(PC1_{slash}_dW))") (class "Default")
      (node (ref "J2") (pin "5") (pinfunction "5_5") (pintype "passive"))
      (node (ref "R3") (pin "1") (pinfunction "1_1") (pintype "passive"))
      (node (ref "U5") (pin "24") (pinfunction "~{Reset}_(PC1_/_dW)_24") (pintype "passive"))
    )
    (net (code "34") (name "Net-(U6-(PCINT0{slash}CLKO{slash}ICP1)_PB0)") (class "Default")
      (node (ref "P2") (pin "8") (pinfunction "8_8") (pintype "passive"))
      (node (ref "U6") (pin "14") (pinfunction "(PCINT0/CLKO/ICP1)_PB0_14") (pintype "passive"))
    )
    (net (code "35") (name "Net-(U6-(PCINT6{slash}XTAL1{slash}TOSC1)_PB6)") (class "Default")
      (node (ref "C14") (pin "2") (pinfunction "2_2") (pintype "passive"))
      (node (ref "R18") (pin "1") (pinfunction "1_1") (pintype "passive"))
      (node (ref "U6") (pin "9") (pinfunction "(PCINT6/XTAL1/TOSC1)_PB6_9") (pintype "passive"))
      (node (ref "Y2") (pin "1") (pinfunction "1_1") (pintype "passive"))
    )
    (net (code "36") (name "Net-(U6-(PCINT7{slash}XTAL2{slash}TOSC2)_PB7)") (class "Default")
      (node (ref "C13") (pin "2") (pinfunction "2_2") (pintype "passive"))
      (node (ref "R18") (pin "2") (pinfunction "2_2") (pintype "passive"))
      (node (ref "U6") (pin "10") (pinfunction "(PCINT7/XTAL2/TOSC2)_PB7_10") (pintype "passive"))
      (node (ref "Y2") (pin "2") (pinfunction "2_2") (pintype "passive"))
    )
    (net (code "37") (name "Net-(U6-(PCINT16{slash}RXD)_PD02)") (class "Default")
      (node (ref "P4") (pin "8") (pinfunction "8_8") (pintype "passive"))
      (node (ref "R19") (pin "2") (pinfunction "2_2") (pintype "passive"))
      (node (ref "U6") (pin "2") (pinfunction "(PCINT16/RXD)_PD02_2") (pintype "passive"))
    )
    (net (code "38") (name "Net-(U6-(PCINT17{slash}TXD)_PD1)") (class "Default")
      (node (ref "P4") (pin "7") (pinfunction "7_7") (pintype "passive"))
      (node (ref "R20") (pin "2") (pinfunction "2_2") (pintype "passive"))
      (node (ref "U6") (pin "3") (pinfunction "(PCINT17/TXD)_PD1_3") (pintype "passive"))
    )
    (net (code "39") (name "Net-(U6-(PCINT18{slash}INT0)_PD2)") (class "Default")
      (node (ref "P4") (pin "6") (pinfunction "6_6") (pintype "passive"))
      (node (ref "U6") (pin "4") (pinfunction "(PCINT18/INT0)_PD2_4") (pintype "passive"))
    )
    (net (code "40") (name "Net-(U6-(PCINT19{slash}OC2B{slash}INT1)_PD3)") (class "Default")
      (node (ref "P4") (pin "5") (pinfunction "5_5") (pintype "passive"))
      (node (ref "U6") (pin "5") (pinfunction "(PCINT19/OC2B/INT1)_PD3_5") (pintype "passive"))
    )
    (net (code "41") (name "Net-(U6-(PCINT20{slash}XCK{slash}T0)_PD4)") (class "Default")
      (node (ref "P4") (pin "4") (pinfunction "4_4") (pintype "passive"))
      (node (ref "U6") (pin "6") (pinfunction "(PCINT20/XCK/T0)_PD4_6") (pintype "passive"))
    )
    (net (code "42") (name "Net-(U6-(PCINT21{slash}OC0B{slash}T1)_PD5)") (class "Default")
      (node (ref "P4") (pin "3") (pinfunction "3_3") (pintype "passive"))
      (node (ref "U6") (pin "11") (pinfunction "(PCINT21/OC0B/T1)_PD5_11") (pintype "passive"))
    )
    (net (code "43") (name "Net-(U6-(PCINT22{slash}OC0A{slash}AIN0)_PD612)") (class "Default")
      (node (ref "P4") (pin "2") (pinfunction "2_2") (pintype "passive"))
      (node (ref "U6") (pin "12") (pinfunction "(PCINT22/OC0A/AIN0)_PD612_12") (pintype "passive"))
    )
    (net (code "44") (name "Net-(U6-(PCINT23{slash}AIN1)_PD7)") (class "Default")
      (node (ref "P4") (pin "1") (pinfunction "1_1") (pintype "passive"))
      (node (ref "U6") (pin "13") (pinfunction "(PCINT23/AIN1)_PD7_13") (pintype "passive"))
    )
    (net (code "45") (name "Net-(U6-PB1_(OC1A{slash}PCINT1))") (class "Default")
      (node (ref "P2") (pin "7") (pinfunction "7_7") (pintype "passive"))
      (node (ref "U6") (pin "15") (pinfunction "PB1_(OC1A/PCINT1)_15") (pintype "passive"))
    )
    (net (code "46") (name "Net-(U6-PB2_(~{SS}{slash}OC1B{slash}PCINT2))") (class "Default")
      (node (ref "P2") (pin "6") (pinfunction "6_6") (pintype "passive"))
      (node (ref "U6") (pin "16") (pinfunction "PB2_(~{SS}/OC1B/PCINT2)_16") (pintype "passive"))
    )
    (net (code "47") (name "Net-(U6-PB3_(MOSI{slash}OC2A{slash}PCINT3))") (class "Default")
      (node (ref "J4") (pin "4") (pinfunction "4_4") (pintype "passive"))
      (node (ref "P2") (pin "5") (pinfunction "5_5") (pintype "passive"))
      (node (ref "U6") (pin "17") (pinfunction "PB3_(MOSI/OC2A/PCINT3)_17") (pintype "passive"))
    )
    (net (code "48") (name "Net-(U6-PB4_(MISO{slash}PCINT4))") (class "Default")
      (node (ref "P2") (pin "4") (pinfunction "4_4") (pintype "passive"))
      (node (ref "U6") (pin "18") (pinfunction "PB4_(MISO/PCINT4)_18") (pintype "passive"))
    )
    (net (code "49") (name "Net-(U6-PB5_(SCK{slash}PCINT5))") (class "Default")
      (node (ref "J4") (pin "3") (pinfunction "3_3") (pintype "passive"))
      (node (ref "P2") (pin "3") (pinfunction "3_3") (pintype "passive"))
      (node (ref "R11") (pin "1") (pinfunction "1_1") (pintype "passive"))
      (node (ref "R12") (pin "1") (pinfunction "1_1") (pintype "passive"))
      (node (ref "U6") (pin "19") (pinfunction "PB5_(SCK/PCINT5)_19") (pintype "passive"))
    )
    (net (code "50") (name "Net-(U6-PC0_(ADC0{slash}PCINT8))") (class "Default")
      (node (ref "P3") (pin "6") (pinfunction "6_6") (pintype "passive"))
      (node (ref "U6") (pin "23") (pinfunction "PC0_(ADC0/PCINT8)_23") (pintype "passive"))
    )
    (net (code "51") (name "Net-(U6-PC1_(ADC1{slash}PCINT9))") (class "Default")
      (node (ref "P3") (pin "5") (pinfunction "5_5") (pintype "passive"))
      (node (ref "U6") (pin "24") (pinfunction "PC1_(ADC1/PCINT9)_24") (pintype "passive"))
    )
    (net (code "52") (name "Net-(U6-PC2_(ADC2{slash}PCINT10))") (class "Default")
      (node (ref "P3") (pin "4") (pinfunction "4_4") (pintype "passive"))
      (node (ref "U6") (pin "25") (pinfunction "PC2_(ADC2/PCINT10)_25") (pintype "passive"))
    )
    (net (code "53") (name "Net-(U6-PC3_(ADC3{slash}PCINT11))") (class "Default")
      (node (ref "P3") (pin "3") (pinfunction "3_3") (pintype "passive"))
      (node (ref "U6") (pin "26") (pinfunction "PC3_(ADC3/PCINT11)_26") (pintype "passive"))
    )
    (net (code "54") (name "Net-(U6-PC4_(ADC4{slash}SDA{slash}PCINT12))") (class "Default")
      (node (ref "P3") (pin "2") (pinfunction "2_2") (pintype "passive"))
      (node (ref "U6") (pin "27") (pinfunction "PC4_(ADC4/SDA/PCINT12)_27") (pintype "passive"))
    )
    (net (code "55") (name "Net-(U6-PC5_(ADC5{slash}SCL{slash}PCINT13))") (class "Default")
      (node (ref "P3") (pin "1") (pinfunction "1_1") (pintype "passive"))
      (node (ref "U6") (pin "28") (pinfunction "PC5_(ADC5/SCL/PCINT13)_28") (pintype "passive"))
    )
    (net (code "56") (name "Net-(U6-PC6_{slash}_PCINT14_{slash}_~{RESET})") (class "Default")
      (node (ref "Button1") (pin "1") (pinfunction "1_1") (pintype "passive"))
      (node (ref "Button1") (pin "2") (pinfunction "2_2") (pintype "passive"))
      (node (ref "C6") (pin "1") (pinfunction "1_1") (pintype "passive"))
      (node (ref "J4") (pin "5") (pinfunction "5_5") (pintype "passive"))
      (node (ref "P1") (pin "6") (pinfunction "6_6") (pintype "passive"))
      (node (ref "R5") (pin "1") (pinfunction "1_1") (pintype "passive"))
      (node (ref "R5") (pin "2") (pinfunction "2_2") (pintype "passive"))
      (node (ref "R8") (pin "2") (pinfunction "2_2") (pintype "passive"))
      (node (ref "U6") (pin "1") (pinfunction "PC6_/_PCINT14_/_~{RESET}_1") (pintype "passive"))
    )
    (net (code "57") (name "unconnected-(J4-Pad1)") (class "Default")
      (node (ref "J4") (pin "1") (pinfunction "1_1") (pintype "passive"))
    )
    (net (code "58") (name "unconnected-(U1B-2OUT-Pad7)") (class "Default")
      (node (ref "U1") (pin "7") (pinfunction "2OUT_7") (pintype "output+no_connect"))
    )
    (net (code "59") (name "unconnected-(U2-GND-Pad1)") (class "Default")
      (node (ref "U2") (pin "1") (pinfunction "GND_1") (pintype "power_in"))
    )
    (net (code "60") (name "unconnected-(U3-NC-Pad5)") (class "Default")
      (node (ref "U3") (pin "5") (pinfunction "NC_5") (pintype "bidirectional+no_connect"))
    )
    (net (code "61") (name "unconnected-(U3-NC-Pad8)") (class "Default")
      (node (ref "U3") (pin "8") (pinfunction "NC_8") (pintype "bidirectional+no_connect"))
    )
    (net (code "62") (name "unconnected-(U4-BYPASS-Pad4)") (class "Default")
      (node (ref "U4") (pin "4") (pinfunction "BYPASS_4") (pintype "bidirectional+no_connect"))
    )
    (net (code "63") (name "unconnected-(U5-(AIN0_{slash}_INT1)_PD1-Pad7)") (class "Default")
      (node (ref "U5") (pin "7") (pinfunction "(AIN0_/_INT1)_PD1_7") (pintype "passive+no_connect"))
    )
    (net (code "64") (name "unconnected-(U5-(OC.0B_{slash}_INT0)_PD0-Pad6)") (class "Default")
      (node (ref "U5") (pin "6") (pinfunction "(OC.0B_/_INT0)_PD0_6") (pintype "passive+no_connect"))
    )
    (net (code "65") (name "unconnected-(U5-(PCINT11_{slash}AIN2_)_PC2-Pad5)") (class "Default")
      (node (ref "U5") (pin "5") (pinfunction "(PCINT11_/AIN2_)_PC2_5") (pintype "passive+no_connect"))
    )
    (net (code "66") (name "unconnected-(U5-(~{RTS}_{slash}_AIN5_{slash}_INT6)_PD6-Pad12)") (class "Default")
      (node (ref "U5") (pin "12") (pinfunction "(~{RTS}_/_AIN5_/_INT6)_PD6_12") (pintype "passive+no_connect"))
    )
    (net (code "67") (name "unconnected-(U5-(~{SS}_{slash}_PCINT0)_PB0-Pad14)") (class "Default")
      (node (ref "U5") (pin "14") (pinfunction "(~{SS}_/_PCINT0)_PB0_14") (pintype "passive"))
    )
    (net (code "68") (name "unconnected-(U5-PB4_(T1_{slash}_PCINT4)-Pad18)") (class "Default")
      (node (ref "U5") (pin "18") (pinfunction "PB4_(T1_/_PCINT4)_18") (pintype "passive+no_connect"))
    )
    (net (code "69") (name "unconnected-(U5-PB5_(PCINT5)-Pad19)") (class "Default")
      (node (ref "U5") (pin "19") (pinfunction "PB5_(PCINT5)_19") (pintype "passive+no_connect"))
    )
    (net (code "70") (name "unconnected-(U5-PB6_(PCINT6)-Pad20)") (class "Default")
      (node (ref "U5") (pin "20") (pinfunction "PB6_(PCINT6)_20") (pintype "passive+no_connect"))
    )
    (net (code "71") (name "unconnected-(U5-PB7_(PCINT7_{slash}_OC.0A_{slash}_OC.1C)-Pad21)") (class "Default")
      (node (ref "U5") (pin "21") (pinfunction "PB7_(PCINT7_/_OC.0A_/_OC.1C)_21") (pintype "passive+no_connect"))
    )
    (net (code "72") (name "unconnected-(U5-PC4_(PCINT10)-Pad26)") (class "Default")
      (node (ref "U5") (pin "26") (pinfunction "PC4_(PCINT10)_26") (pintype "passive+no_connect"))
    )
    (net (code "73") (name "unconnected-(U5-PC5_(_PCINT9{slash}_OC.1B)-Pad25)") (class "Default")
      (node (ref "U5") (pin "25") (pinfunction "PC5_(_PCINT9/_OC.1B)_25") (pintype "passive+no_connect"))
    )
    (net (code "74") (name "unconnected-(U5-PC6_(OC.1A_{slash}_PCINT8)-Pad23)") (class "Default")
      (node (ref "U5") (pin "23") (pinfunction "PC6_(OC.1A_/_PCINT8)_23") (pintype "passive+no_connect"))
    )
    (net (code "75") (name "unconnected-(U5-PC7_(INT4_{slash}_ICP1_{slash}_CLKO)-Pad22)") (class "Default")
      (node (ref "U5") (pin "22") (pinfunction "PC7_(INT4_/_ICP1_/_CLKO)_22") (pintype "passive+no_connect"))
    )
  )
)
